# ESP12_DEV_01.net
KiCad netlist of a schematic drawn in Altium Designer
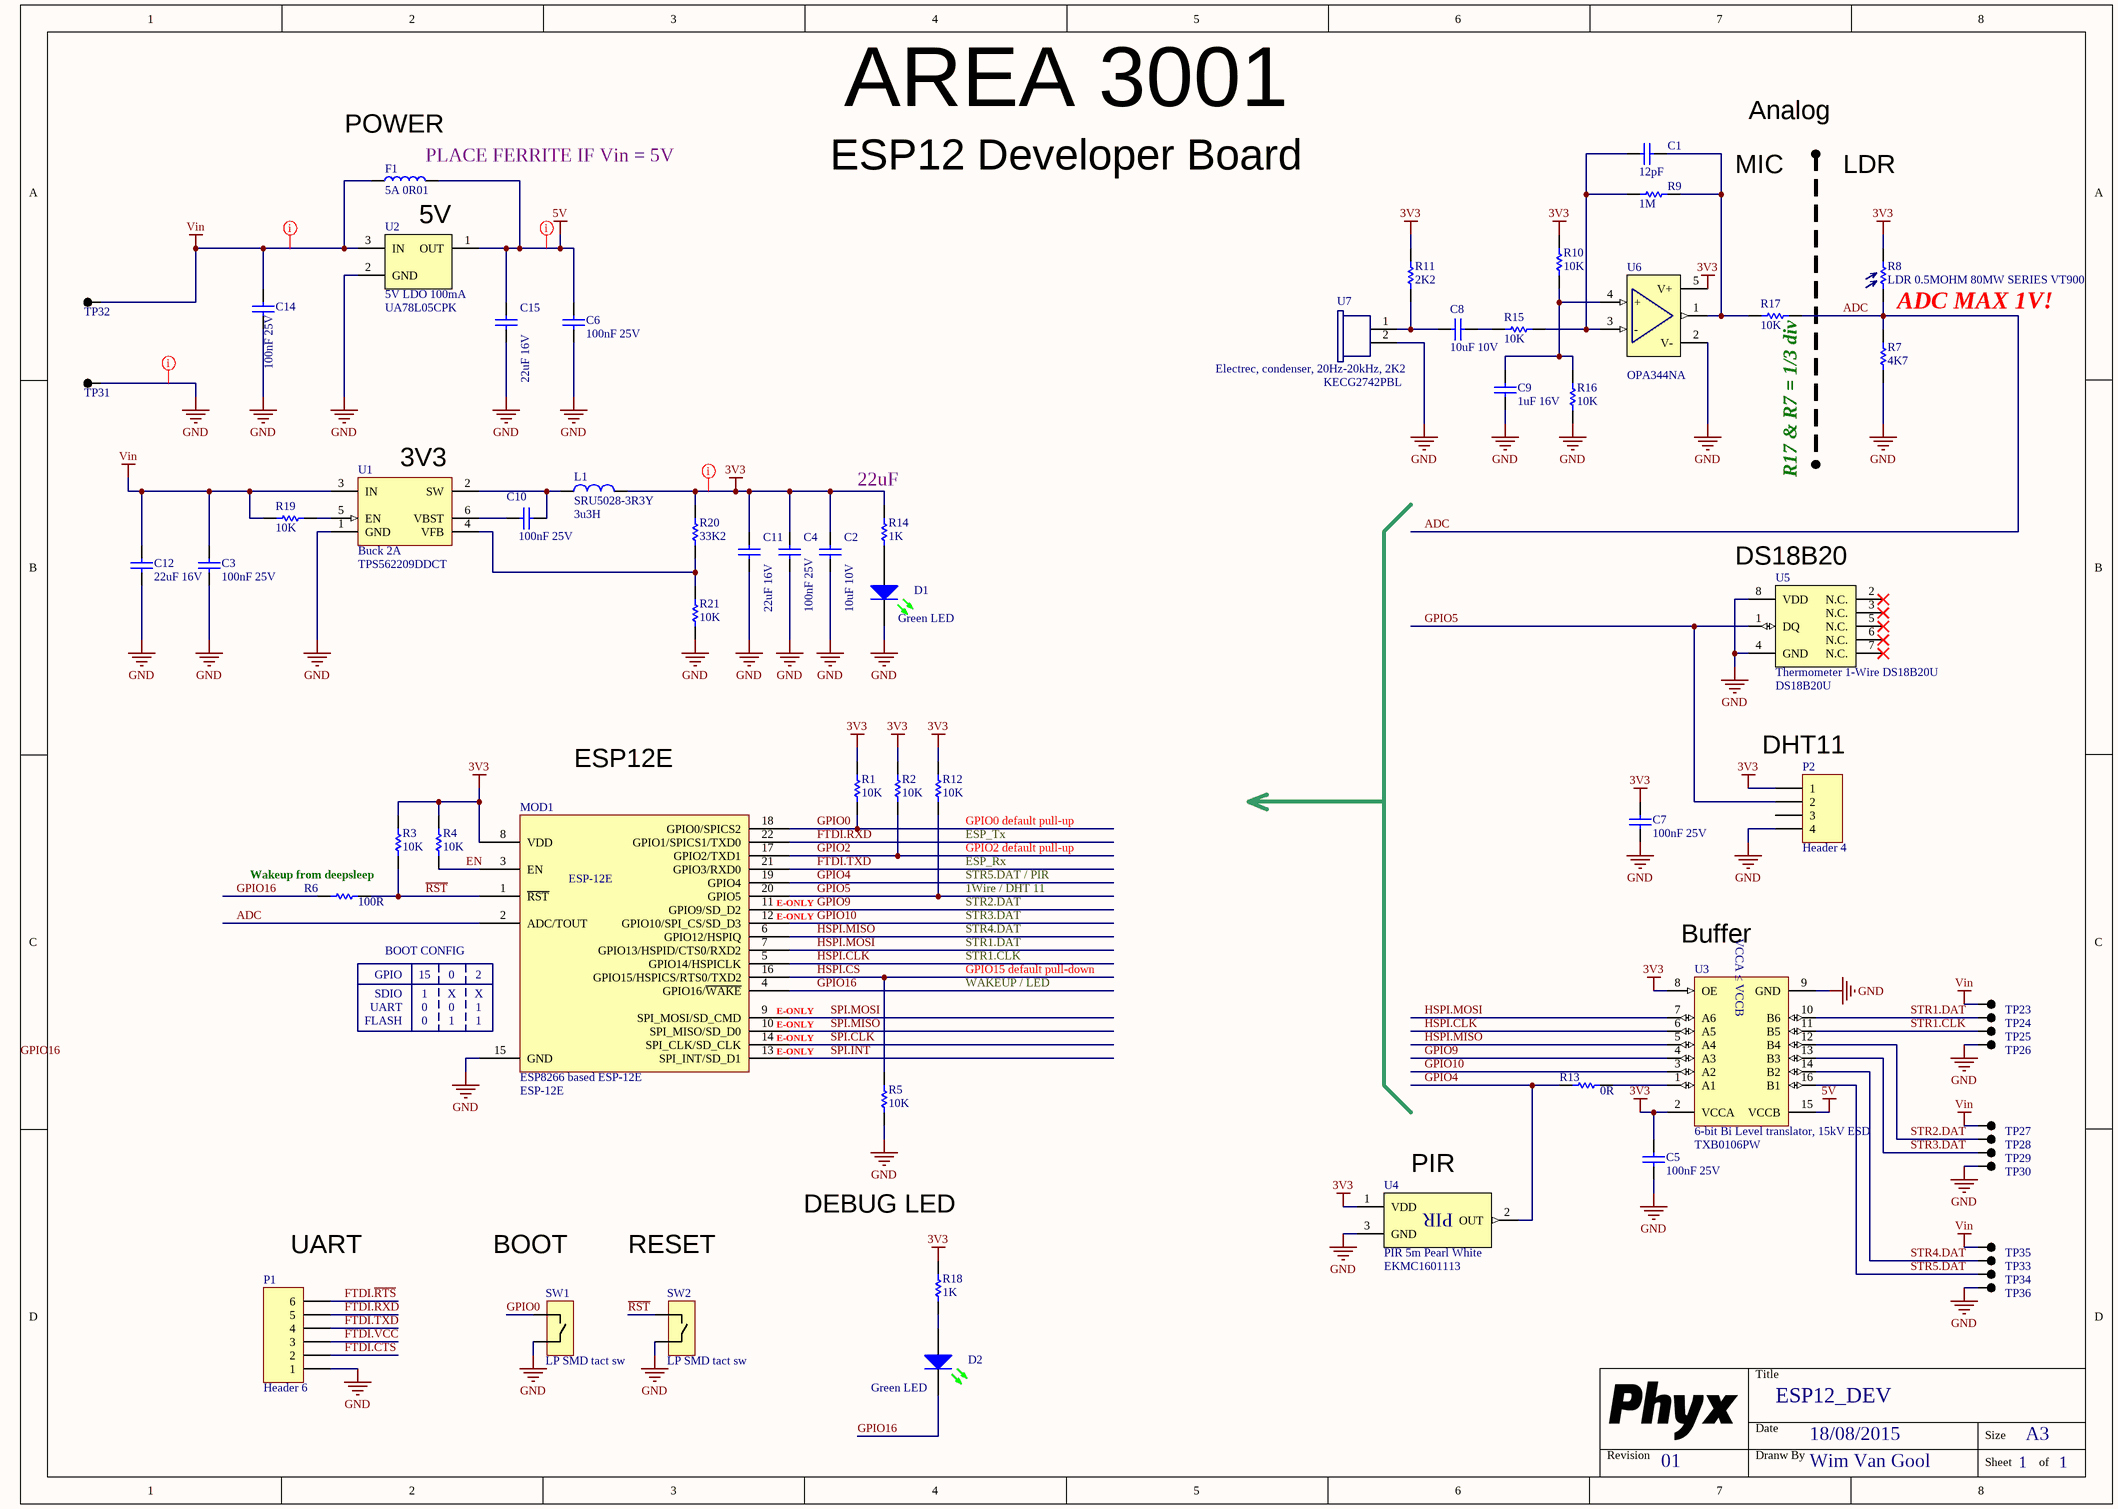
[diagram p0: ESP12_DEV_01.SchDoc]

(export (version "E")
  (design (tool "Eeschema 10.0.6"))
  (components
    (comp (ref "C1")
      (value "12pF")
      (footprint "C0603")
      (description "Capacitor Ceramic")
      (fields (field (name "Comment") "CAP_CERAMIC"))
      (libsource (lib "Phyx_Components") (part "CAP_CERAMIC"))
    )
    (comp (ref "C2")
      (value "10uF 10V")
      (footprint "C0805")
      (description "Capacitor Ceramic")
      (fields (field (name "Comment") "CAP_CERAMIC"))
      (libsource (lib "Phyx_Components") (part "CAP_CERAMIC"))
    )
    (comp (ref "C3")
      (value "100nF 25V")
      (footprint "C0805")
      (description "Capacitor Ceramic")
      (fields (field (name "Comment") "CAP_CERAMIC"))
      (libsource (lib "Phyx_Components") (part "CAP_CERAMIC"))
    )
    (comp (ref "C4")
      (value "100nF 25V")
      (footprint "C0805")
      (description "Capacitor Ceramic")
      (fields (field (name "Comment") "CAP_CERAMIC"))
      (libsource (lib "Phyx_Components") (part "CAP_CERAMIC"))
    )
    (comp (ref "C5")
      (value "100nF 25V")
      (footprint "C0805")
      (description "Capacitor Ceramic")
      (fields (field (name "Comment") "CAP_CERAMIC"))
      (libsource (lib "Phyx_Components") (part "CAP_CERAMIC"))
    )
    (comp (ref "C6")
      (value "100nF 25V")
      (footprint "C0805")
      (description "Capacitor Ceramic")
      (fields (field (name "Comment") "CAP_CERAMIC"))
      (libsource (lib "Phyx_Components") (part "CAP_CERAMIC"))
    )
    (comp (ref "C7")
      (value "100nF 25V")
      (footprint "C0805")
      (description "Capacitor Ceramic")
      (fields (field (name "Comment") "CAP_CERAMIC"))
      (libsource (lib "Phyx_Components") (part "CAP_CERAMIC"))
    )
    (comp (ref "C8")
      (value "10uF 10V")
      (footprint "C0805")
      (description "Capacitor Ceramic")
      (fields (field (name "Comment") "CAP_CERAMIC"))
      (libsource (lib "Phyx_Components") (part "CAP_CERAMIC"))
    )
    (comp (ref "C9")
      (value "1uF 16V")
      (footprint "C0603")
      (description "Capacitor Ceramic")
      (fields (field (name "Comment") "CAP_CERAMIC"))
      (libsource (lib "Phyx_Components") (part "CAP_CERAMIC"))
    )
    (comp (ref "C10")
      (value "100nF 25V")
      (footprint "C0805")
      (description "Capacitor Ceramic")
      (fields (field (name "Comment") "CAP_CERAMIC"))
      (libsource (lib "Phyx_Components") (part "CAP_CERAMIC"))
    )
    (comp (ref "C11")
      (value "22uF 16V")
      (footprint "C1206")
      (description "Capacitor Ceramic")
      (fields (field (name "Comment") "CAP_CERAMIC"))
      (libsource (lib "Phyx_Components") (part "CAP_CERAMIC"))
    )
    (comp (ref "C12")
      (value "22uF 16V")
      (footprint "C1206")
      (description "Capacitor Ceramic")
      (fields (field (name "Comment") "CAP_CERAMIC"))
      (libsource (lib "Phyx_Components") (part "CAP_CERAMIC"))
    )
    (comp (ref "C14")
      (value "100nF 25V")
      (footprint "C0805")
      (description "Capacitor Ceramic")
      (fields (field (name "Comment") "CAP_CERAMIC"))
      (libsource (lib "Phyx_Components") (part "CAP_CERAMIC"))
    )
    (comp (ref "C15")
      (value "22uF 16V")
      (footprint "C1206")
      (description "Capacitor Ceramic")
      (fields (field (name "Comment") "CAP_CERAMIC"))
      (libsource (lib "Phyx_Components") (part "CAP_CERAMIC"))
    )
    (comp (ref "D1")
      (value "Green LED")
      (footprint "LED_0805_GR")
      (description "=Description")
      (libsource (lib "Phyx_Components") (part "LED_GREEN"))
    )
    (comp (ref "D2")
      (value "Green LED")
      (footprint "LED_0805_GR")
      (description "=Description")
      (libsource (lib "Phyx_Components") (part "LED_GREEN"))
    )
    (comp (ref "F1")
      (value "5A 0R01")
      (footprint "L0805")
      (fields (field (name "Comment") "FERRITE"))
      (libsource (lib "Phyx_Components") (part "FERRITE"))
    )
    (comp (ref "L1")
      (value "SRU5028-3R3Y")
      (footprint "BRNS_SRU5028")
      (fields (field (name "ALTIUM_VALUE") "3u3H"))
      (libsource (lib "Phyx_Components") (part "INDUCTOR"))
    )
    (comp (ref "MOD1")
      (value "ESP8266 based ESP-12E")
      (footprint "ESP-12E")
      (description "=Description")
      (fields (field (name "ALTIUM_VALUE") "ESP-12E"))
      (libsource (lib "Phyx_Components") (part "ESP-12E"))
    )
    (comp (ref "P1")
      (value "Header 6")
      (footprint "HDR1X6")
      (libsource (lib "Phyx_Components") (part "Header 6"))
    )
    (comp (ref "P2")
      (value "Header 4")
      (footprint "HDR1X4")
      (libsource (lib "Phyx_Components") (part "Header 4"))
    )
    (comp (ref "R1")
      (value "10K")
      (footprint "R0603")
      (fields (field (name "Comment") "RESISTOR"))
      (libsource (lib "Phyx_Components") (part "RESISTOR"))
    )
    (comp (ref "R2")
      (value "10K")
      (footprint "R0603")
      (fields (field (name "Comment") "RESISTOR"))
      (libsource (lib "Phyx_Components") (part "RESISTOR"))
    )
    (comp (ref "R3")
      (value "10K")
      (footprint "R0603")
      (fields (field (name "Comment") "RESISTOR"))
      (libsource (lib "Phyx_Components") (part "RESISTOR"))
    )
    (comp (ref "R4")
      (value "10K")
      (footprint "R0603")
      (fields (field (name "Comment") "RESISTOR"))
      (libsource (lib "Phyx_Components") (part "RESISTOR"))
    )
    (comp (ref "R5")
      (value "10K")
      (footprint "R0603")
      (fields (field (name "Comment") "RESISTOR"))
      (libsource (lib "Phyx_Components") (part "RESISTOR"))
    )
    (comp (ref "R6")
      (value "100R")
      (footprint "R0603")
      (fields (field (name "Comment") "RESISTOR"))
      (libsource (lib "Phyx_Components") (part "RESISTOR"))
    )
    (comp (ref "R7")
      (value "4K7")
      (footprint "R0603")
      (fields (field (name "Comment") "RESISTOR"))
      (libsource (lib "Phyx_Components") (part "RESISTOR"))
    )
    (comp (ref "R8")
      (value "LDR 0.5MOHM 80MW SERIES VT900")
      (footprint "VT900")
      (description "=Description")
      (libsource (lib "Phyx_Components") (part "LDR_2"))
    )
    (comp (ref "R9")
      (value "1M")
      (footprint "R0603")
      (fields (field (name "Comment") "RESISTOR"))
      (libsource (lib "Phyx_Components") (part "RESISTOR"))
    )
    (comp (ref "R10")
      (value "10K")
      (footprint "R0603")
      (fields (field (name "Comment") "RESISTOR"))
      (libsource (lib "Phyx_Components") (part "RESISTOR"))
    )
    (comp (ref "R11")
      (value "2K2")
      (footprint "R0603")
      (fields (field (name "Comment") "RESISTOR"))
      (libsource (lib "Phyx_Components") (part "RESISTOR"))
    )
    (comp (ref "R12")
      (value "10K")
      (footprint "R0603")
      (fields (field (name "Comment") "RESISTOR"))
      (libsource (lib "Phyx_Components") (part "RESISTOR"))
    )
    (comp (ref "R13")
      (value "0R")
      (footprint "R0603")
      (fields (field (name "Comment") "RESISTOR"))
      (libsource (lib "Phyx_Components") (part "RESISTOR"))
    )
    (comp (ref "R14")
      (value "1K")
      (footprint "R0603")
      (fields (field (name "Comment") "RESISTOR"))
      (libsource (lib "Phyx_Components") (part "RESISTOR"))
    )
    (comp (ref "R15")
      (value "10K")
      (footprint "R0603")
      (fields (field (name "Comment") "RESISTOR"))
      (libsource (lib "Phyx_Components") (part "RESISTOR"))
    )
    (comp (ref "R16")
      (value "10K")
      (footprint "R0603")
      (fields (field (name "Comment") "RESISTOR"))
      (libsource (lib "Phyx_Components") (part "RESISTOR"))
    )
    (comp (ref "R17")
      (value "10K")
      (footprint "R0603")
      (fields (field (name "Comment") "RESISTOR"))
      (libsource (lib "Phyx_Components") (part "RESISTOR"))
    )
    (comp (ref "R18")
      (value "1K")
      (footprint "R0603")
      (fields (field (name "Comment") "RESISTOR"))
      (libsource (lib "Phyx_Components") (part "RESISTOR"))
    )
    (comp (ref "R19")
      (value "10K")
      (footprint "R0603")
      (fields (field (name "Comment") "RESISTOR"))
      (libsource (lib "Phyx_Components") (part "RESISTOR"))
    )
    (comp (ref "R20")
      (value "33K2")
      (footprint "R0603")
      (fields (field (name "Comment") "RESISTOR"))
      (libsource (lib "Phyx_Components") (part "RESISTOR"))
    )
    (comp (ref "R21")
      (value "10K")
      (footprint "R0603")
      (fields (field (name "Comment") "RESISTOR"))
      (libsource (lib "Phyx_Components") (part "RESISTOR"))
    )
    (comp (ref "SW1")
      (value "LP SMD tact sw")
      (footprint "CK_KMR4")
      (libsource (lib "Phyx_Components") (part "SW_TACT"))
    )
    (comp (ref "SW2")
      (value "LP SMD tact sw")
      (footprint "CK_KMR4")
      (libsource (lib "Phyx_Components") (part "SW_TACT"))
    )
    (comp (ref "TP23")
      (value "TEST_PAD")
      (footprint "TP_2x3mm")
      (libsource (lib "Phyx_Components") (part "TEST_PAD"))
    )
    (comp (ref "TP24")
      (value "TEST_PAD")
      (footprint "TP_2x3mm")
      (libsource (lib "Phyx_Components") (part "TEST_PAD"))
    )
    (comp (ref "TP25")
      (value "TEST_PAD")
      (footprint "TP_2x3mm")
      (libsource (lib "Phyx_Components") (part "TEST_PAD"))
    )
    (comp (ref "TP26")
      (value "TEST_PAD")
      (footprint "TP_2x3mm")
      (libsource (lib "Phyx_Components") (part "TEST_PAD"))
    )
    (comp (ref "TP27")
      (value "TEST_PAD")
      (footprint "TP_2x3mm")
      (libsource (lib "Phyx_Components") (part "TEST_PAD"))
    )
    (comp (ref "TP28")
      (value "TEST_PAD")
      (footprint "TP_2x3mm")
      (libsource (lib "Phyx_Components") (part "TEST_PAD"))
    )
    (comp (ref "TP29")
      (value "TEST_PAD")
      (footprint "TP_2x3mm")
      (libsource (lib "Phyx_Components") (part "TEST_PAD"))
    )
    (comp (ref "TP30")
      (value "TEST_PAD")
      (footprint "TP_2x3mm")
      (libsource (lib "Phyx_Components") (part "TEST_PAD"))
    )
    (comp (ref "TP31")
      (value "TEST_PAD")
      (footprint "TP_2x3mm")
      (libsource (lib "Phyx_Components") (part "TEST_PAD"))
    )
    (comp (ref "TP32")
      (value "TEST_PAD")
      (footprint "TP_2x3mm")
      (libsource (lib "Phyx_Components") (part "TEST_PAD"))
    )
    (comp (ref "TP33")
      (value "TEST_PAD")
      (footprint "TP_2x3mm")
      (libsource (lib "Phyx_Components") (part "TEST_PAD"))
    )
    (comp (ref "TP34")
      (value "TEST_PAD")
      (footprint "TP_2x3mm")
      (libsource (lib "Phyx_Components") (part "TEST_PAD"))
    )
    (comp (ref "TP35")
      (value "TEST_PAD")
      (footprint "TP_2x3mm")
      (libsource (lib "Phyx_Components") (part "TEST_PAD"))
    )
    (comp (ref "TP36")
      (value "TEST_PAD")
      (footprint "TP_2x3mm")
      (libsource (lib "Phyx_Components") (part "TEST_PAD"))
    )
    (comp (ref "U1")
      (value "Buck 2A")
      (footprint "TI_DDC_R-PDSO-G6")
      (description "=Description")
      (fields (field (name "ALTIUM_VALUE") "TPS562209DDCT"))
      (libsource (lib "Phyx_Components") (part "TPS56x209"))
    )
    (comp (ref "U2")
      (value "5V LDO 100mA")
      (footprint "TI_PK")
      (description "LDO 5V 100mA")
      (fields (field (name "ALTIUM_VALUE") "UA78L05CPK"))
      (libsource (lib "Phyx_Components") (part "UA78L05CPK"))
    )
    (comp (ref "U3")
      (value "6-bit Bi Level translator, 15kV ESD")
      (footprint "TI_PW_R-PDSO-G16")
      (description "=Description")
      (fields (field (name "ALTIUM_VALUE") "TXB0106PW"))
      (libsource (lib "Phyx_Components") (part "TXB0106PW"))
    )
    (comp (ref "U4")
      (value "PIR 5m Pearl White")
      (footprint "PAN_EKMC1601113")
      (description "=Description")
      (fields (field (name "ALTIUM_VALUE") "EKMC1601113"))
      (libsource (lib "Phyx_Components") (part "EKMC160x111x"))
    )
    (comp (ref "U5")
      (value "Thermometer 1-Wire DS18B20U")
      (footprint "MAX_uSOP8")
      (description "=Description")
      (fields (field (name "ALTIUM_VALUE") "DS18B20U"))
      (libsource (lib "Phyx_Components") (part "DS18B20U"))
    )
    (comp (ref "U6")
      (value "OPA344NA")
      (footprint "TI_DBV_R-PDSO-G5")
      (description "=Description")
      (fields (field (name "Comment") "Low Power, Single supply, Rail-to-Rail opamp"))
      (libsource (lib "Phyx_Components") (part "OPA34xNA"))
    )
    (comp (ref "U7")
      (value "Electrec, condenser, 20Hz-20kHz, 2K2")
      (footprint "MIC_2742PB")
      (description "=Description")
      (fields (field (name "ALTIUM_VALUE") "KECG2742PBL"))
      (libsource (lib "Phyx_Components") (part "MIC_ELEC_2"))
    )
  )
  (nets
    (net (code "1") (name "/ADC") (class "Default")
      (node (ref "MOD1") (pin "2") (pinfunction "ADC/TOUT_2") (pintype "passive"))
      (node (ref "R17") (pin "1") (pinfunction "1_1") (pintype "passive"))
      (node (ref "R7") (pin "1") (pinfunction "1_1") (pintype "passive"))
      (node (ref "R8") (pin "2") (pinfunction "2_2") (pintype "passive"))
    )
    (net (code "2") (name "/EN") (class "Default")
      (node (ref "MOD1") (pin "3") (pinfunction "EN_3") (pintype "passive"))
      (node (ref "R4") (pin "2") (pinfunction "2_2") (pintype "passive"))
    )
    (net (code "3") (name "/FTDI.RXD") (class "Default")
      (node (ref "MOD1") (pin "22") (pinfunction "GPIO1/SPICS1/TXD0_22") (pintype "passive"))
      (node (ref "P1") (pin "5") (pinfunction "5_5") (pintype "passive"))
    )
    (net (code "4") (name "/FTDI.TXD") (class "Default")
      (node (ref "MOD1") (pin "21") (pinfunction "GPIO3/RXD0_21") (pintype "passive"))
      (node (ref "P1") (pin "4") (pinfunction "4_4") (pintype "passive"))
    )
    (net (code "5") (name "/FTDI.VCC") (class "Default")
      (node (ref "P1") (pin "3") (pinfunction "3_3") (pintype "passive"))
    )
    (net (code "6") (name "/FTDI.~{CTS}") (class "Default")
      (node (ref "P1") (pin "2") (pinfunction "2_2") (pintype "passive"))
    )
    (net (code "7") (name "/FTDI.~{RTS}") (class "Default")
      (node (ref "P1") (pin "6") (pinfunction "6_6") (pintype "passive"))
    )
    (net (code "8") (name "/GPIO0") (class "Default")
      (node (ref "MOD1") (pin "18") (pinfunction "GPIO0/SPICS2_18") (pintype "passive"))
      (node (ref "R1") (pin "2") (pinfunction "2_2") (pintype "passive"))
      (node (ref "SW1") (pin "1") (pinfunction "1_1") (pintype "passive"))
    )
    (net (code "9") (name "/GPIO2") (class "Default")
      (node (ref "MOD1") (pin "17") (pinfunction "GPIO2/TXD1_17") (pintype "passive"))
      (node (ref "R2") (pin "2") (pinfunction "2_2") (pintype "passive"))
    )
    (net (code "10") (name "/GPIO4") (class "Default")
      (node (ref "MOD1") (pin "19") (pinfunction "GPIO4_19") (pintype "passive"))
      (node (ref "R13") (pin "2") (pinfunction "2_2") (pintype "passive"))
      (node (ref "U4") (pin "2") (pinfunction "OUT_2") (pintype "output"))
    )
    (net (code "11") (name "/GPIO5") (class "Default")
      (node (ref "MOD1") (pin "20") (pinfunction "GPIO5_20") (pintype "passive"))
      (node (ref "P2") (pin "2") (pinfunction "2_2") (pintype "passive"))
      (node (ref "R12") (pin "2") (pinfunction "2_2") (pintype "passive"))
      (node (ref "U5") (pin "1") (pinfunction "DQ_1") (pintype "bidirectional"))
    )
    (net (code "12") (name "/GPIO9") (class "Default")
      (node (ref "MOD1") (pin "11") (pinfunction "GPIO9/SD_D2_11") (pintype "passive"))
      (node (ref "U3") (pin "4") (pinfunction "A3_4") (pintype "bidirectional"))
    )
    (net (code "13") (name "/GPIO10") (class "Default")
      (node (ref "MOD1") (pin "12") (pinfunction "GPIO10/SPI_CS/SD_D3_12") (pintype "passive"))
      (node (ref "U3") (pin "3") (pinfunction "A2_3") (pintype "bidirectional"))
    )
    (net (code "14") (name "/GPIO16") (class "Default")
      (node (ref "D2") (pin "2") (pinfunction "K_2") (pintype "passive"))
      (node (ref "MOD1") (pin "4") (pinfunction "GPIO16/~{WAKE}_4") (pintype "passive"))
      (node (ref "R6") (pin "2") (pinfunction "2_2") (pintype "passive"))
    )
    (net (code "15") (name "/HSPI.CLK") (class "Default")
      (node (ref "MOD1") (pin "5") (pinfunction "GPIO14/HSPICLK_5") (pintype "passive"))
      (node (ref "U3") (pin "6") (pinfunction "A5_6") (pintype "bidirectional"))
    )
    (net (code "16") (name "/HSPI.CS") (class "Default")
      (node (ref "MOD1") (pin "16") (pinfunction "GPIO15/HSPICS/RTS0/TXD2_16") (pintype "passive"))
      (node (ref "R5") (pin "1") (pinfunction "1_1") (pintype "passive"))
    )
    (net (code "17") (name "/HSPI.MISO") (class "Default")
      (node (ref "MOD1") (pin "6") (pinfunction "GPIO12/HSPIQ_6") (pintype "passive"))
      (node (ref "U3") (pin "5") (pinfunction "A4_5") (pintype "bidirectional"))
    )
    (net (code "18") (name "/HSPI.MOSI") (class "Default")
      (node (ref "MOD1") (pin "7") (pinfunction "GPIO13/HSPID/CTS0/RXD2_7") (pintype "passive"))
      (node (ref "U3") (pin "7") (pinfunction "A6_7") (pintype "bidirectional"))
    )
    (net (code "19") (name "/SPI.CLK") (class "Default")
      (node (ref "MOD1") (pin "14") (pinfunction "SPI_CLK/SD_CLK_14") (pintype "passive"))
    )
    (net (code "20") (name "/SPI.INT") (class "Default")
      (node (ref "MOD1") (pin "13") (pinfunction "SPI_INT/SD_D1_13") (pintype "passive"))
    )
    (net (code "21") (name "/SPI.MISO") (class "Default")
      (node (ref "MOD1") (pin "10") (pinfunction "SPI_MISO/SD_D0_10") (pintype "passive"))
    )
    (net (code "22") (name "/SPI.MOSI") (class "Default")
      (node (ref "MOD1") (pin "9") (pinfunction "SPI_MOSI/SD_CMD_9") (pintype "passive"))
    )
    (net (code "23") (name "/STR1.CLK") (class "Default")
      (node (ref "TP25") (pin "1") (pinfunction "1_1") (pintype "passive"))
      (node (ref "U3") (pin "11") (pinfunction "B5_11") (pintype "bidirectional"))
    )
    (net (code "24") (name "/STR1.DAT") (class "Default")
      (node (ref "TP24") (pin "1") (pinfunction "1_1") (pintype "passive"))
      (node (ref "U3") (pin "10") (pinfunction "B6_10") (pintype "bidirectional"))
    )
    (net (code "25") (name "/STR2.DAT") (class "Default")
      (node (ref "TP28") (pin "1") (pinfunction "1_1") (pintype "passive"))
      (node (ref "U3") (pin "12") (pinfunction "B4_12") (pintype "bidirectional"))
    )
    (net (code "26") (name "/STR3.DAT") (class "Default")
      (node (ref "TP29") (pin "1") (pinfunction "1_1") (pintype "passive"))
      (node (ref "U3") (pin "13") (pinfunction "B3_13") (pintype "bidirectional"))
    )
    (net (code "27") (name "/STR4.DAT") (class "Default")
      (node (ref "TP33") (pin "1") (pinfunction "1_1") (pintype "passive"))
      (node (ref "U3") (pin "14") (pinfunction "B2_14") (pintype "bidirectional"))
    )
    (net (code "28") (name "/STR5.DAT") (class "Default")
      (node (ref "TP34") (pin "1") (pinfunction "1_1") (pintype "passive"))
      (node (ref "U3") (pin "16") (pinfunction "B1_16") (pintype "bidirectional"))
    )
    (net (code "29") (name "/~{RST}") (class "Default")
      (node (ref "MOD1") (pin "1") (pinfunction "~{RST}_1") (pintype "passive"))
      (node (ref "R3") (pin "2") (pinfunction "2_2") (pintype "passive"))
      (node (ref "R6") (pin "1") (pinfunction "1_1") (pintype "passive"))
      (node (ref "SW2") (pin "1") (pinfunction "1_1") (pintype "passive"))
    )
    (net (code "30") (name "3V3") (class "Default")
      (node (ref "C11") (pin "1") (pinfunction "1_1") (pintype "passive"))
      (node (ref "C2") (pin "1") (pinfunction "1_1") (pintype "passive"))
      (node (ref "C4") (pin "1") (pinfunction "1_1") (pintype "passive"))
      (node (ref "C5") (pin "1") (pinfunction "1_1") (pintype "passive"))
      (node (ref "C7") (pin "1") (pinfunction "1_1") (pintype "passive"))
      (node (ref "L1") (pin "2") (pinfunction "2_2") (pintype "passive"))
      (node (ref "MOD1") (pin "8") (pinfunction "VDD_8") (pintype "passive"))
      (node (ref "P2") (pin "1") (pinfunction "1_1") (pintype "passive"))
      (node (ref "R1") (pin "1") (pinfunction "1_1") (pintype "passive"))
      (node (ref "R10") (pin "2") (pinfunction "2_2") (pintype "passive"))
      (node (ref "R11") (pin "1") (pinfunction "1_1") (pintype "passive"))
      (node (ref "R12") (pin "1") (pinfunction "1_1") (pintype "passive"))
      (node (ref "R14") (pin "1") (pinfunction "1_1") (pintype "passive"))
      (node (ref "R18") (pin "1") (pinfunction "1_1") (pintype "passive"))
      (node (ref "R2") (pin "1") (pinfunction "1_1") (pintype "passive"))
      (node (ref "R20") (pin "1") (pinfunction "1_1") (pintype "passive"))
      (node (ref "R3") (pin "1") (pinfunction "1_1") (pintype "passive"))
      (node (ref "R4") (pin "1") (pinfunction "1_1") (pintype "passive"))
      (node (ref "R8") (pin "1") (pinfunction "1_1") (pintype "passive"))
      (node (ref "U3") (pin "2") (pinfunction "VCCA_2") (pintype "power_in"))
      (node (ref "U3") (pin "8") (pinfunction "OE_8") (pintype "input"))
      (node (ref "U4") (pin "1") (pinfunction "VDD_1") (pintype "power_in"))
      (node (ref "U6") (pin "5") (pinfunction "V+_5") (pintype "power_in"))
    )
    (net (code "31") (name "5V") (class "Default")
      (node (ref "C15") (pin "1") (pinfunction "1_1") (pintype "passive"))
      (node (ref "C6") (pin "1") (pinfunction "1_1") (pintype "passive"))
      (node (ref "F1") (pin "2") (pinfunction "2_2") (pintype "passive"))
      (node (ref "U2") (pin "1") (pinfunction "OUT_1") (pintype "passive"))
      (node (ref "U3") (pin "15") (pinfunction "VCCB_15") (pintype "power_in"))
    )
    (net (code "32") (name "GND") (class "Default")
      (node (ref "C11") (pin "2") (pinfunction "2_2") (pintype "passive"))
      (node (ref "C12") (pin "2") (pinfunction "2_2") (pintype "passive"))
      (node (ref "C14") (pin "1") (pinfunction "1_1") (pintype "passive"))
      (node (ref "C15") (pin "2") (pinfunction "2_2") (pintype "passive"))
      (node (ref "C2") (pin "2") (pinfunction "2_2") (pintype "passive"))
      (node (ref "C3") (pin "2") (pinfunction "2_2") (pintype "passive"))
      (node (ref "C4") (pin "2") (pinfunction "2_2") (pintype "passive"))
      (node (ref "C5") (pin "2") (pinfunction "2_2") (pintype "passive"))
      (node (ref "C6") (pin "2") (pinfunction "2_2") (pintype "passive"))
      (node (ref "C7") (pin "2") (pinfunction "2_2") (pintype "passive"))
      (node (ref "C9") (pin "2") (pinfunction "2_2") (pintype "passive"))
      (node (ref "D1") (pin "2") (pinfunction "K_2") (pintype "passive"))
      (node (ref "MOD1") (pin "15") (pinfunction "GND_15") (pintype "passive"))
      (node (ref "P1") (pin "1") (pinfunction "1_1") (pintype "passive"))
      (node (ref "P2") (pin "4") (pinfunction "4_4") (pintype "passive"))
      (node (ref "R16") (pin "1") (pinfunction "1_1") (pintype "passive"))
      (node (ref "R21") (pin "1") (pinfunction "1_1") (pintype "passive"))
      (node (ref "R5") (pin "2") (pinfunction "2_2") (pintype "passive"))
      (node (ref "R7") (pin "2") (pinfunction "2_2") (pintype "passive"))
      (node (ref "SW1") (pin "2") (pinfunction "2_2") (pintype "passive"))
      (node (ref "SW2") (pin "2") (pinfunction "2_2") (pintype "passive"))
      (node (ref "TP26") (pin "1") (pinfunction "1_1") (pintype "passive"))
      (node (ref "TP30") (pin "1") (pinfunction "1_1") (pintype "passive"))
      (node (ref "TP31") (pin "1") (pinfunction "1_1") (pintype "passive"))
      (node (ref "TP36") (pin "1") (pinfunction "1_1") (pintype "passive"))
      (node (ref "U1") (pin "1") (pinfunction "GND_1") (pintype "power_in"))
      (node (ref "U2") (pin "2") (pinfunction "GND_2") (pintype "passive"))
      (node (ref "U3") (pin "9") (pinfunction "GND_9") (pintype "power_in"))
      (node (ref "U4") (pin "3") (pinfunction "GND_3") (pintype "power_in"))
      (node (ref "U5") (pin "4") (pinfunction "GND_4") (pintype "power_in"))
      (node (ref "U5") (pin "8") (pinfunction "VDD_8") (pintype "power_in"))
      (node (ref "U6") (pin "2") (pinfunction "V-_2") (pintype "power_in"))
      (node (ref "U7") (pin "2") (pinfunction "2_2") (pintype "passive"))
    )
    (net (code "33") (name "Net-(C8-Pad1)") (class "Default")
      (node (ref "C8") (pin "1") (pinfunction "1_1") (pintype "passive"))
      (node (ref "R15") (pin "2") (pinfunction "2_2") (pintype "passive"))
    )
    (net (code "34") (name "Net-(C8-Pad2)") (class "Default")
      (node (ref "C8") (pin "2") (pinfunction "2_2") (pintype "passive"))
      (node (ref "R11") (pin "2") (pinfunction "2_2") (pintype "passive"))
      (node (ref "U7") (pin "1") (pinfunction "1_1") (pintype "passive"))
    )
    (net (code "35") (name "Net-(D1-A)") (class "Default")
      (node (ref "D1") (pin "1") (pinfunction "A_1") (pintype "passive"))
      (node (ref "R14") (pin "2") (pinfunction "2_2") (pintype "passive"))
    )
    (net (code "36") (name "Net-(D2-A)") (class "Default")
      (node (ref "D2") (pin "1") (pinfunction "A_1") (pintype "passive"))
      (node (ref "R18") (pin "2") (pinfunction "2_2") (pintype "passive"))
    )
    (net (code "37") (name "Net-(U1-EN)") (class "Default")
      (node (ref "R19") (pin "1") (pinfunction "1_1") (pintype "passive"))
      (node (ref "U1") (pin "5") (pinfunction "EN_5") (pintype "input"))
    )
    (net (code "38") (name "Net-(U1-SW)") (class "Default")
      (node (ref "C10") (pin "1") (pinfunction "1_1") (pintype "passive"))
      (node (ref "L1") (pin "1") (pinfunction "1_1") (pintype "passive"))
      (node (ref "U1") (pin "2") (pinfunction "SW_2") (pintype "power_in"))
    )
    (net (code "39") (name "Net-(U1-VBST)") (class "Default")
      (node (ref "C10") (pin "2") (pinfunction "2_2") (pintype "passive"))
      (node (ref "U1") (pin "6") (pinfunction "VBST_6") (pintype "power_in"))
    )
    (net (code "40") (name "Net-(U1-VFB)") (class "Default")
      (node (ref "R20") (pin "2") (pinfunction "2_2") (pintype "passive"))
      (node (ref "R21") (pin "2") (pinfunction "2_2") (pintype "passive"))
      (node (ref "U1") (pin "4") (pinfunction "VFB_4") (pintype "passive"))
    )
    (net (code "41") (name "Net-(U3-A1)") (class "Default")
      (node (ref "R13") (pin "1") (pinfunction "1_1") (pintype "passive"))
      (node (ref "U3") (pin "1") (pinfunction "A1_1") (pintype "bidirectional"))
    )
    (net (code "42") (name "Net-(U6-+)") (class "Default")
      (node (ref "C9") (pin "1") (pinfunction "1_1") (pintype "passive"))
      (node (ref "R10") (pin "1") (pinfunction "1_1") (pintype "passive"))
      (node (ref "R16") (pin "2") (pinfunction "2_2") (pintype "passive"))
      (node (ref "U6") (pin "4") (pinfunction "+_4") (pintype "input"))
    )
    (net (code "43") (name "Net-(U6--)") (class "Default")
      (node (ref "C1") (pin "2") (pinfunction "2_2") (pintype "passive"))
      (node (ref "R15") (pin "1") (pinfunction "1_1") (pintype "passive"))
      (node (ref "R9") (pin "2") (pinfunction "2_2") (pintype "passive"))
      (node (ref "U6") (pin "3") (pinfunction "-_3") (pintype "input"))
    )
    (net (code "44") (name "Net-(U6-OUT)") (class "Default")
      (node (ref "C1") (pin "1") (pinfunction "1_1") (pintype "passive"))
      (node (ref "R17") (pin "2") (pinfunction "2_2") (pintype "passive"))
      (node (ref "R9") (pin "1") (pinfunction "1_1") (pintype "passive"))
      (node (ref "U6") (pin "1") (pinfunction "OUT_1") (pintype "output"))
    )
    (net (code "45") (name "Vin") (class "Default")
      (node (ref "C12") (pin "1") (pinfunction "1_1") (pintype "passive"))
      (node (ref "C14") (pin "2") (pinfunction "2_2") (pintype "passive"))
      (node (ref "C3") (pin "1") (pinfunction "1_1") (pintype "passive"))
      (node (ref "F1") (pin "1") (pinfunction "1_1") (pintype "passive"))
      (node (ref "R19") (pin "2") (pinfunction "2_2") (pintype "passive"))
      (node (ref "TP23") (pin "1") (pinfunction "1_1") (pintype "passive"))
      (node (ref "TP27") (pin "1") (pinfunction "1_1") (pintype "passive"))
      (node (ref "TP32") (pin "1") (pinfunction "1_1") (pintype "passive"))
      (node (ref "TP35") (pin "1") (pinfunction "1_1") (pintype "passive"))
      (node (ref "U1") (pin "3") (pinfunction "IN_3") (pintype "power_in"))
      (node (ref "U2") (pin "3") (pinfunction "IN_3") (pintype "passive"))
    )
    (net (code "46") (name "unconnected-(P2-Pad3)") (class "Default")
      (node (ref "P2") (pin "3") (pinfunction "3_3") (pintype "passive"))
    )
    (net (code "47") (name "unconnected-(U5-N.C.-Pad2)") (class "Default")
      (node (ref "U5") (pin "2") (pinfunction "N.C._2") (pintype "passive+no_connect"))
    )
    (net (code "48") (name "unconnected-(U5-N.C.-Pad3)") (class "Default")
      (node (ref "U5") (pin "3") (pinfunction "N.C._3") (pintype "passive+no_connect"))
    )
    (net (code "49") (name "unconnected-(U5-N.C.-Pad5)") (class "Default")
      (node (ref "U5") (pin "5") (pinfunction "N.C._5") (pintype "passive+no_connect"))
    )
    (net (code "50") (name "unconnected-(U5-N.C.-Pad6)") (class "Default")
      (node (ref "U5") (pin "6") (pinfunction "N.C._6") (pintype "passive+no_connect"))
    )
    (net (code "51") (name "unconnected-(U5-N.C.-Pad7)") (class "Default")
      (node (ref "U5") (pin "7") (pinfunction "N.C._7") (pintype "passive+no_connect"))
    )
  )
)
